# AdEMNEA.net
KiCad netlist of a schematic drawn in EasyEDA
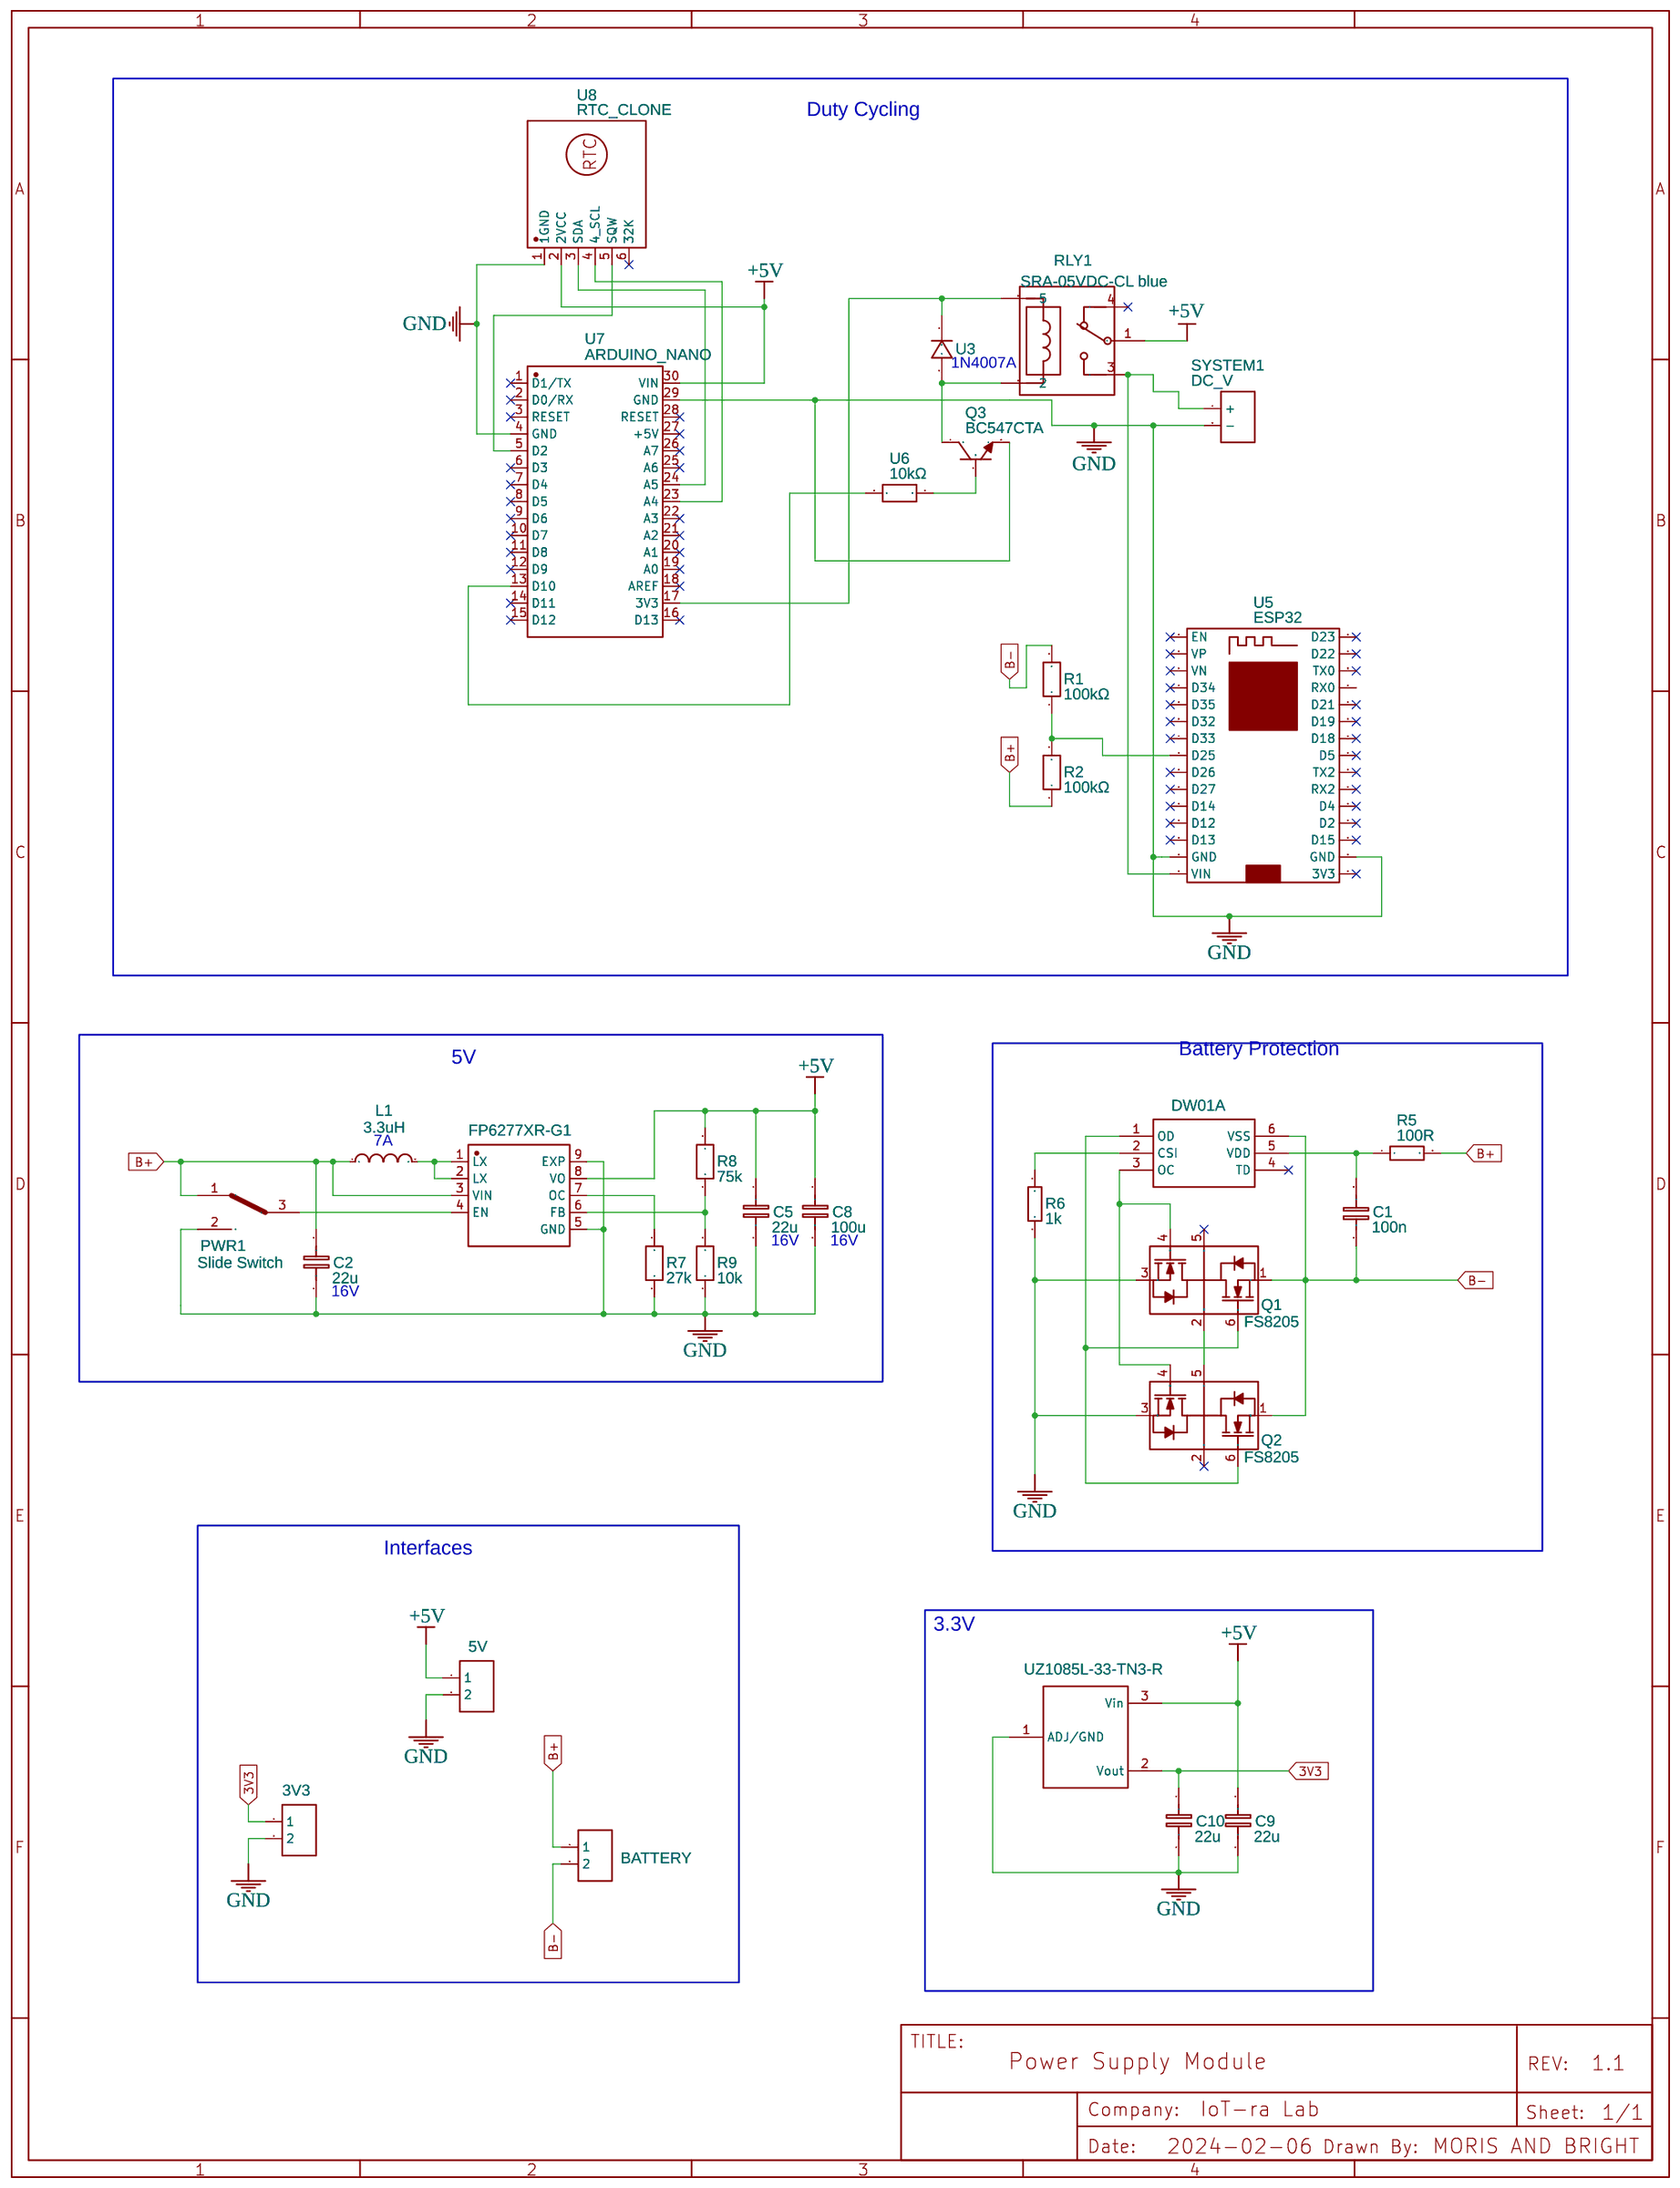
[diagram p0: schematic sheet]

(export (version "E")
  (design (tool "Eeschema 10.0.6"))
  (components
    (comp (ref "3V3")
      (value "Connector")
      (fields (field (name "Manufacturer Part") "2.54-1*2PFemale") (field (name "Manufacturer") "BOOMELE"))
      (libsource (lib "") (part "Unknown_305_-960"))
    )
    (comp (ref "5V")
      (value "Connector")
      (fields (field (name "Manufacturer Part") "2.54-1*2PFemale") (field (name "Manufacturer") "BOOMELE"))
      (libsource (lib "") (part "Unknown_410_-1045"))
    )
    (comp (ref "BATTERY")
      (value "Connector")
      (fields (field (name "Manufacturer Part") "2.54-1*2PFemale") (field (name "Manufacturer") "BOOMELE"))
      (libsource (lib "") (part "Unknown_480_-945"))
    )
    (comp (ref "C1")
      (value "100n")
      (fields (field (name "Manufacturer Part") "CC0805KRX7R9BB104") (field (name "Manufacturer") "YAGEO"))
      (libsource (lib "") (part "Cap_0805_EU_1"))
    )
    (comp (ref "C2")
      (value "22u")
      (fields (field (name "Manufacturer Part") "CL21A226MAQNNNE") (field (name "Manufacturer") "SAMSUNG"))
      (libsource (lib "") (part "Cap_0805_EU_2"))
    )
    (comp (ref "C5")
      (value "22u")
      (fields (field (name "Manufacturer Part") "CL21A226MAQNNNE") (field (name "Manufacturer") "SAMSUNG"))
      (libsource (lib "") (part "Cap_0805_EU"))
    )
    (comp (ref "C8")
      (value "100u")
      (fields (field (name "Manufacturer Part") "CL31A107MPHNNNE") (field (name "Manufacturer") "SAMSUNG"))
      (libsource (lib "") (part "Cap_0805_EU"))
    )
    (comp (ref "C9")
      (value "22u")
      (fields (field (name "Manufacturer Part") "CL21A226MAQNNNE") (field (name "Manufacturer") "SAMSUNG"))
      (libsource (lib "") (part "Cap_0805_EU"))
    )
    (comp (ref "C10")
      (value "22u")
      (fields (field (name "Manufacturer Part") "CL21A226MAQNNNE") (field (name "Manufacturer") "SAMSUNG"))
      (libsource (lib "") (part "Cap_0805_EU"))
    )
    (comp (ref "L1")
      (value "3.3uH")
      (fields (field (name "Manufacturer Part") "JSHC0650H-3R3M-G") (field (name "Manufacturer") "Jinlai"))
      (libsource (lib "") (part "JSHC0650H-3R3M-G"))
    )
    (comp (ref "PWR1")
      (value "Slide Switch")
      (fields (field (name "Manufacturer Part") "New SchematicLib"))
      (libsource (lib "") (part "Unknown_280_-1325"))
    )
    (comp (ref "Q1")
      (value "FS8205")
      (fields (field (name "Manufacturer") "FORTUNE"))
      (libsource (lib "") (part "FS8205"))
    )
    (comp (ref "Q2")
      (value "FS8205")
      (fields (field (name "Manufacturer") "FORTUNE"))
      (libsource (lib "") (part "FS8205"))
    )
    (comp (ref "Q3")
      (value "BC547CTA")
      (fields (field (name "Manufacturer") "onsemi(安森美)"))
      (libsource (lib "") (part "BC547CTA"))
    )
    (comp (ref "R1")
      (value "100kΩ")
      (fields
        (field (name "Manufacturer Part") "RNF14FAE100K")
        (field (name "Manufacturer") "SEI(Stackpole Electronics Inc.)")
      )
      (libsource (lib "") (part "RNF14FAE100K"))
    )
    (comp (ref "R2")
      (value "100kΩ")
      (fields
        (field (name "Manufacturer Part") "RNF14FAE100K")
        (field (name "Manufacturer") "SEI(Stackpole Electronics Inc.)")
      )
      (libsource (lib "") (part "RNF14FAE100K"))
    )
    (comp (ref "R5")
      (value "100R")
      (fields (field (name "Manufacturer Part") "0805W8F1000T5E") (field (name "Manufacturer") "UniOhm"))
      (libsource (lib "") (part "Res_0805(1/8W)_EU"))
    )
    (comp (ref "R6")
      (value "1k")
      (fields (field (name "Manufacturer Part") "0805W8F1001T5E") (field (name "Manufacturer") "UniOhm"))
      (libsource (lib "") (part "Res_0805(1/8W)_EU_2"))
    )
    (comp (ref "R7")
      (value "27k")
      (fields (field (name "Manufacturer Part") "0805W8F2702T5E") (field (name "Manufacturer") "UniOhm"))
      (libsource (lib "") (part "Res_0805(1/8W)_EU_1"))
    )
    (comp (ref "R8")
      (value "75k")
      (fields (field (name "Manufacturer Part") "0805W8F7502T5E") (field (name "Manufacturer") "UniOhm"))
      (libsource (lib "") (part "Res_0805(1/8W)_EU_1"))
    )
    (comp (ref "R9")
      (value "10k")
      (fields (field (name "Manufacturer Part") "0805W8F1002T5E") (field (name "Manufacturer") "UniOhm"))
      (libsource (lib "") (part "Res_0805(1/8W)_EU_1"))
    )
    (comp (ref "RLY1")
      (value "SRA-05VDC-CL blue")
      (fields (field (name "Manufacturer Part") "SRA-05VDC-CL") (field (name "Manufacturer") "松乐"))
      (libsource (lib "") (part "SRA-05VDC-CL blue"))
    )
    (comp (ref "SYSTEM1") (value "DC_V") (libsource (lib "") (part "DC_V")))
    (comp (ref "U1")
      (value "FP6277XR-G1")
      (fields (field (name "Manufacturer") "Feeling Technology"))
      (libsource (lib "") (part "FP6277XR-G1"))
    )
    (comp (ref "U2")
      (value "DW01A")
      (fields (field (name "Manufacturer") "FM"))
      (libsource (lib "") (part "Unknown_845_-1360"))
    )
    (comp (ref "U3")
      (value "1N4007A")
      (fields (field (name "Manufacturer") "LRC(乐山无线电)"))
      (libsource (lib "") (part "1N4007A"))
    )
    (comp (ref "U4")
      (value "UZ1085L-33-TN3-R")
      (fields (field (name "Manufacturer") "UTC"))
      (libsource (lib "") (part "UZ1085L-33-TN3-R"))
    )
    (comp (ref "U5") (value "ESP32") (libsource (lib "") (part "ESP32")))
    (comp (ref "U6")
      (value "10kΩ")
      (fields (field (name "Manufacturer Part") "FM0207FTE52-10K") (field (name "Manufacturer") "YAGEO(国巨)"))
      (libsource (lib "") (part "FM0207FTE52-10K"))
    )
    (comp (ref "U7") (value "ARDUINO_NANO") (libsource (lib "") (part "ARDUINO_NANO")))
    (comp (ref "U8") (value "RTC_CLONE") (libsource (lib "") (part "RTC_CLONE")))
  )
  (nets
    (net (code "1") (name "+5V") (class "Default")
      (node (ref "5V") (pin "1") (pinfunction "1_1") (pintype "input"))
      (node (ref "C5") (pin "1") (pinfunction "1_1") (pintype "unspecified"))
      (node (ref "C8") (pin "1") (pinfunction "1_1") (pintype "unspecified"))
      (node (ref "C9") (pin "1") (pinfunction "1_1") (pintype "unspecified"))
      (node (ref "R8") (pin "2") (pinfunction "2_2") (pintype "unspecified"))
      (node (ref "RLY1") (pin "1") (pinfunction "1_1") (pintype "unspecified"))
      (node (ref "U1") (pin "8") (pinfunction "VO_8") (pintype "unspecified"))
      (node (ref "U4") (pin "3") (pinfunction "Vin_3") (pintype "unspecified"))
      (node (ref "U7") (pin "30") (pinfunction "VIN_30") (pintype "unspecified"))
      (node (ref "U8") (pin "2") (pinfunction "2VCC_2") (pintype "unspecified"))
    )
    (net (code "2") (name "3V3") (class "Default")
      (node (ref "3V3") (pin "1") (pinfunction "1_1") (pintype "input"))
      (node (ref "C10") (pin "1") (pinfunction "1_1") (pintype "unspecified"))
      (node (ref "U4") (pin "2") (pinfunction "Vout_2") (pintype "unspecified"))
    )
    (net (code "3") (name "B+") (class "Default")
      (node (ref "BATTERY") (pin "1") (pinfunction "1_1") (pintype "input"))
      (node (ref "C2") (pin "1") (pinfunction "1_1") (pintype "unspecified"))
      (node (ref "L1") (pin "1") (pinfunction "1_1") (pintype "unspecified"))
      (node (ref "PWR1") (pin "1") (pinfunction "1_1") (pintype "unspecified"))
      (node (ref "R2") (pin "1") (pinfunction "1_1") (pintype "unspecified"))
      (node (ref "R5") (pin "2") (pinfunction "2_2") (pintype "unspecified"))
      (node (ref "U1") (pin "3") (pinfunction "VIN_3") (pintype "unspecified"))
    )
    (net (code "4") (name "B-") (class "Default")
      (node (ref "BATTERY") (pin "2") (pinfunction "2_2") (pintype "input"))
      (node (ref "C1") (pin "1") (pinfunction "1_1") (pintype "unspecified"))
      (node (ref "Q1") (pin "1") (pinfunction "S1_1") (pintype "unspecified"))
      (node (ref "Q2") (pin "1") (pinfunction "S1_1") (pintype "unspecified"))
      (node (ref "R1") (pin "2") (pinfunction "2_2") (pintype "unspecified"))
      (node (ref "U2") (pin "6") (pinfunction "VSS_6") (pintype "unspecified"))
    )
    (net (code "5") (name "GND") (class "Default")
      (node (ref "3V3") (pin "2") (pinfunction "2_2") (pintype "input"))
      (node (ref "5V") (pin "2") (pinfunction "2_2") (pintype "input"))
      (node (ref "C10") (pin "2") (pinfunction "2_2") (pintype "unspecified"))
      (node (ref "C2") (pin "2") (pinfunction "2_2") (pintype "unspecified"))
      (node (ref "C5") (pin "2") (pinfunction "2_2") (pintype "unspecified"))
      (node (ref "C8") (pin "2") (pinfunction "2_2") (pintype "unspecified"))
      (node (ref "C9") (pin "2") (pinfunction "2_2") (pintype "unspecified"))
      (node (ref "PWR1") (pin "2") (pinfunction "2_2") (pintype "unspecified"))
      (node (ref "Q1") (pin "3") (pinfunction "S2_3") (pintype "unspecified"))
      (node (ref "Q2") (pin "3") (pinfunction "S2_3") (pintype "unspecified"))
      (node (ref "Q3") (pin "3") (pinfunction "E_3") (pintype "input"))
      (node (ref "R6") (pin "1") (pinfunction "1_1") (pintype "unspecified"))
      (node (ref "R7") (pin "1") (pinfunction "1_1") (pintype "unspecified"))
      (node (ref "R9") (pin "1") (pinfunction "1_1") (pintype "unspecified"))
      (node (ref "SYSTEM1") (pin "2") (pinfunction "-_2") (pintype "unspecified"))
      (node (ref "U1") (pin "5") (pinfunction "GND_5") (pintype "unspecified"))
      (node (ref "U1") (pin "9") (pinfunction "EXP_9") (pintype "unspecified"))
      (node (ref "U4") (pin "1") (pinfunction "ADJ/GND_1") (pintype "unspecified"))
      (node (ref "U5") (pin "14") (pinfunction "GND_14") (pintype "unspecified"))
      (node (ref "U5") (pin "17") (pinfunction "GND_17") (pintype "unspecified"))
      (node (ref "U7") (pin "29") (pinfunction "GND_29") (pintype "unspecified"))
      (node (ref "U7") (pin "4") (pinfunction "GND_4") (pintype "unspecified"))
      (node (ref "U8") (pin "1") (pinfunction "1GND_1") (pintype "unspecified"))
    )
    (net (code "6") (name "Net-(L1-Pad2)") (class "Default")
      (node (ref "L1") (pin "2") (pinfunction "2_2") (pintype "unspecified"))
      (node (ref "U1") (pin "1") (pinfunction "LX_1") (pintype "unspecified"))
      (node (ref "U1") (pin "2") (pinfunction "LX_2") (pintype "unspecified"))
    )
    (net (code "7") (name "Net-(Q1-D12-Pad2)") (class "Default")
      (node (ref "Q1") (pin "2") (pinfunction "D12_2") (pintype "unspecified"))
      (node (ref "Q2") (pin "5") (pinfunction "D12_5") (pintype "unspecified"))
    )
    (net (code "8") (name "Net-(Q1-G1)") (class "Default")
      (node (ref "Q1") (pin "6") (pinfunction "G1_6") (pintype "unspecified"))
      (node (ref "Q2") (pin "6") (pinfunction "G1_6") (pintype "unspecified"))
      (node (ref "U2") (pin "1") (pinfunction "OD_1") (pintype "unspecified"))
    )
    (net (code "9") (name "Net-(Q1-G2)") (class "Default")
      (node (ref "Q1") (pin "4") (pinfunction "G2_4") (pintype "unspecified"))
      (node (ref "Q2") (pin "4") (pinfunction "G2_4") (pintype "unspecified"))
      (node (ref "U2") (pin "3") (pinfunction "OC_3") (pintype "unspecified"))
    )
    (net (code "10") (name "Net-(Q3-B)") (class "Default")
      (node (ref "Q3") (pin "2") (pinfunction "B_2") (pintype "input"))
      (node (ref "U6") (pin "2") (pinfunction "2_2") (pintype "unspecified"))
    )
    (net (code "11") (name "Net-(Q3-C)") (class "Default")
      (node (ref "Q3") (pin "1") (pinfunction "C_1") (pintype "input"))
      (node (ref "RLY1") (pin "2") (pinfunction "2_2") (pintype "unspecified"))
      (node (ref "U3") (pin "2") (pinfunction "2_2") (pintype "unspecified"))
    )
    (net (code "12") (name "Net-(SYSTEM1-+)") (class "Default")
      (node (ref "RLY1") (pin "3") (pinfunction "3_3") (pintype "unspecified"))
      (node (ref "SYSTEM1") (pin "1") (pinfunction "+_1") (pintype "unspecified"))
      (node (ref "U5") (pin "15") (pinfunction "VIN_15") (pintype "unspecified"))
    )
    (net (code "13") (name "Net-(U1-EN)") (class "Default")
      (node (ref "PWR1") (pin "3") (pinfunction "3_3") (pintype "unspecified"))
      (node (ref "U1") (pin "4") (pinfunction "EN_4") (pintype "unspecified"))
    )
    (net (code "14") (name "Net-(U1-FB)") (class "Default")
      (node (ref "R8") (pin "1") (pinfunction "1_1") (pintype "unspecified"))
      (node (ref "R9") (pin "2") (pinfunction "2_2") (pintype "unspecified"))
      (node (ref "U1") (pin "6") (pinfunction "FB_6") (pintype "unspecified"))
    )
    (net (code "15") (name "Net-(U1-OC)") (class "Default")
      (node (ref "R7") (pin "2") (pinfunction "2_2") (pintype "unspecified"))
      (node (ref "U1") (pin "7") (pinfunction "OC_7") (pintype "unspecified"))
    )
    (net (code "16") (name "Net-(U2-CSI)") (class "Default")
      (node (ref "R6") (pin "2") (pinfunction "2_2") (pintype "unspecified"))
      (node (ref "U2") (pin "2") (pinfunction "CSI_2") (pintype "unspecified"))
    )
    (net (code "17") (name "Net-(U2-VDD)") (class "Default")
      (node (ref "C1") (pin "2") (pinfunction "2_2") (pintype "unspecified"))
      (node (ref "R5") (pin "1") (pinfunction "1_1") (pintype "unspecified"))
      (node (ref "U2") (pin "5") (pinfunction "VDD_5") (pintype "unspecified"))
    )
    (net (code "18") (name "Net-(U5-D25)") (class "Default")
      (node (ref "R1") (pin "1") (pinfunction "1_1") (pintype "unspecified"))
      (node (ref "R2") (pin "2") (pinfunction "2_2") (pintype "unspecified"))
      (node (ref "U5") (pin "8") (pinfunction "D25_8") (pintype "unspecified"))
    )
    (net (code "19") (name "Net-(U7-3V3)") (class "Default")
      (node (ref "RLY1") (pin "5") (pinfunction "5_5") (pintype "unspecified"))
      (node (ref "U3") (pin "1") (pinfunction "1_1") (pintype "unspecified"))
      (node (ref "U7") (pin "17") (pinfunction "3V3_17") (pintype "unspecified"))
    )
    (net (code "20") (name "Net-(U7-A4)") (class "Default")
      (node (ref "U7") (pin "23") (pinfunction "A4_23") (pintype "unspecified"))
      (node (ref "U8") (pin "4") (pinfunction "4_SCL_4") (pintype "unspecified"))
    )
    (net (code "21") (name "Net-(U7-A5)") (class "Default")
      (node (ref "U7") (pin "24") (pinfunction "A5_24") (pintype "unspecified"))
      (node (ref "U8") (pin "3") (pinfunction "SDA_3") (pintype "unspecified"))
    )
    (net (code "22") (name "Net-(U7-D2)") (class "Default")
      (node (ref "U7") (pin "5") (pinfunction "D2_5") (pintype "unspecified"))
      (node (ref "U8") (pin "5") (pinfunction "SQW_5") (pintype "unspecified"))
    )
    (net (code "23") (name "Net-(U7-D10)") (class "Default")
      (node (ref "U6") (pin "1") (pinfunction "1_1") (pintype "unspecified"))
      (node (ref "U7") (pin "13") (pinfunction "D10_13") (pintype "unspecified"))
    )
    (net (code "24") (name "unconnected-(Q1-D12-Pad5)") (class "Default")
      (node (ref "Q1") (pin "5") (pinfunction "D12_5") (pintype "unspecified+no_connect"))
    )
    (net (code "25") (name "unconnected-(Q2-D12-Pad2)") (class "Default")
      (node (ref "Q2") (pin "2") (pinfunction "D12_2") (pintype "unspecified+no_connect"))
    )
    (net (code "26") (name "unconnected-(RLY1-Pad4)") (class "Default")
      (node (ref "RLY1") (pin "4") (pinfunction "4_4") (pintype "unspecified+no_connect"))
    )
    (net (code "27") (name "unconnected-(U2-TD-Pad4)") (class "Default")
      (node (ref "U2") (pin "4") (pinfunction "TD_4") (pintype "unspecified+no_connect"))
    )
    (net (code "28") (name "unconnected-(U5-3V3-Pad16)") (class "Default")
      (node (ref "U5") (pin "16") (pinfunction "3V3_16") (pintype "unspecified+no_connect"))
    )
    (net (code "29") (name "unconnected-(U5-D2-Pad19)") (class "Default")
      (node (ref "U5") (pin "19") (pinfunction "D2_19") (pintype "unspecified+no_connect"))
    )
    (net (code "30") (name "unconnected-(U5-D4-Pad20)") (class "Default")
      (node (ref "U5") (pin "20") (pinfunction "D4_20") (pintype "unspecified+no_connect"))
    )
    (net (code "31") (name "unconnected-(U5-D5-Pad23)") (class "Default")
      (node (ref "U5") (pin "23") (pinfunction "D5_23") (pintype "unspecified+no_connect"))
    )
    (net (code "32") (name "unconnected-(U5-D12-Pad12)") (class "Default")
      (node (ref "U5") (pin "12") (pinfunction "D12_12") (pintype "unspecified+no_connect"))
    )
    (net (code "33") (name "unconnected-(U5-D13-Pad13)") (class "Default")
      (node (ref "U5") (pin "13") (pinfunction "D13_13") (pintype "unspecified+no_connect"))
    )
    (net (code "34") (name "unconnected-(U5-D14-Pad11)") (class "Default")
      (node (ref "U5") (pin "11") (pinfunction "D14_11") (pintype "unspecified+no_connect"))
    )
    (net (code "35") (name "unconnected-(U5-D15-Pad18)") (class "Default")
      (node (ref "U5") (pin "18") (pinfunction "D15_18") (pintype "unspecified+no_connect"))
    )
    (net (code "36") (name "unconnected-(U5-D18-Pad24)") (class "Default")
      (node (ref "U5") (pin "24") (pinfunction "D18_24") (pintype "unspecified+no_connect"))
    )
    (net (code "37") (name "unconnected-(U5-D19-Pad25)") (class "Default")
      (node (ref "U5") (pin "25") (pinfunction "D19_25") (pintype "unspecified+no_connect"))
    )
    (net (code "38") (name "unconnected-(U5-D21-Pad26)") (class "Default")
      (node (ref "U5") (pin "26") (pinfunction "D21_26") (pintype "unspecified+no_connect"))
    )
    (net (code "39") (name "unconnected-(U5-D22-Pad29)") (class "Default")
      (node (ref "U5") (pin "29") (pinfunction "D22_29") (pintype "unspecified+no_connect"))
    )
    (net (code "40") (name "unconnected-(U5-D23-Pad30)") (class "Default")
      (node (ref "U5") (pin "30") (pinfunction "D23_30") (pintype "unspecified+no_connect"))
    )
    (net (code "41") (name "unconnected-(U5-D26-Pad9)") (class "Default")
      (node (ref "U5") (pin "9") (pinfunction "D26_9") (pintype "unspecified+no_connect"))
    )
    (net (code "42") (name "unconnected-(U5-D27-Pad10)") (class "Default")
      (node (ref "U5") (pin "10") (pinfunction "D27_10") (pintype "unspecified+no_connect"))
    )
    (net (code "43") (name "unconnected-(U5-D32-Pad6)") (class "Default")
      (node (ref "U5") (pin "6") (pinfunction "D32_6") (pintype "unspecified+no_connect"))
    )
    (net (code "44") (name "unconnected-(U5-D33-Pad7)") (class "Default")
      (node (ref "U5") (pin "7") (pinfunction "D33_7") (pintype "unspecified+no_connect"))
    )
    (net (code "45") (name "unconnected-(U5-D34-Pad4)") (class "Default")
      (node (ref "U5") (pin "4") (pinfunction "D34_4") (pintype "unspecified+no_connect"))
    )
    (net (code "46") (name "unconnected-(U5-D35-Pad5)") (class "Default")
      (node (ref "U5") (pin "5") (pinfunction "D35_5") (pintype "unspecified+no_connect"))
    )
    (net (code "47") (name "unconnected-(U5-EN-Pad1)") (class "Default")
      (node (ref "U5") (pin "1") (pinfunction "EN_1") (pintype "unspecified+no_connect"))
    )
    (net (code "48") (name "unconnected-(U5-RX0-Pad27)") (class "Default")
      (node (ref "U5") (pin "27") (pinfunction "RX0_27") (pintype "unspecified"))
    )
    (net (code "49") (name "unconnected-(U5-RX2-Pad21)") (class "Default")
      (node (ref "U5") (pin "21") (pinfunction "RX2_21") (pintype "unspecified+no_connect"))
    )
    (net (code "50") (name "unconnected-(U5-TX0-Pad28)") (class "Default")
      (node (ref "U5") (pin "28") (pinfunction "TX0_28") (pintype "unspecified+no_connect"))
    )
    (net (code "51") (name "unconnected-(U5-TX2-Pad22)") (class "Default")
      (node (ref "U5") (pin "22") (pinfunction "TX2_22") (pintype "unspecified+no_connect"))
    )
    (net (code "52") (name "unconnected-(U5-VN-Pad3)") (class "Default")
      (node (ref "U5") (pin "3") (pinfunction "VN_3") (pintype "unspecified+no_connect"))
    )
    (net (code "53") (name "unconnected-(U5-VP-Pad2)") (class "Default")
      (node (ref "U5") (pin "2") (pinfunction "VP_2") (pintype "unspecified+no_connect"))
    )
    (net (code "54") (name "unconnected-(U7-+5V-Pad27)") (class "Default")
      (node (ref "U7") (pin "27") (pinfunction "+5V_27") (pintype "unspecified+no_connect"))
    )
    (net (code "55") (name "unconnected-(U7-A0-Pad19)") (class "Default")
      (node (ref "U7") (pin "19") (pinfunction "A0_19") (pintype "unspecified+no_connect"))
    )
    (net (code "56") (name "unconnected-(U7-A1-Pad20)") (class "Default")
      (node (ref "U7") (pin "20") (pinfunction "A1_20") (pintype "unspecified+no_connect"))
    )
    (net (code "57") (name "unconnected-(U7-A2-Pad21)") (class "Default")
      (node (ref "U7") (pin "21") (pinfunction "A2_21") (pintype "unspecified+no_connect"))
    )
    (net (code "58") (name "unconnected-(U7-A3-Pad22)") (class "Default")
      (node (ref "U7") (pin "22") (pinfunction "A3_22") (pintype "unspecified+no_connect"))
    )
    (net (code "59") (name "unconnected-(U7-A6-Pad25)") (class "Default")
      (node (ref "U7") (pin "25") (pinfunction "A6_25") (pintype "unspecified+no_connect"))
    )
    (net (code "60") (name "unconnected-(U7-A7-Pad26)") (class "Default")
      (node (ref "U7") (pin "26") (pinfunction "A7_26") (pintype "unspecified+no_connect"))
    )
    (net (code "61") (name "unconnected-(U7-AREF-Pad18)") (class "Default")
      (node (ref "U7") (pin "18") (pinfunction "AREF_18") (pintype "unspecified+no_connect"))
    )
    (net (code "62") (name "unconnected-(U7-D0{slash}RX-Pad2)") (class "Default")
      (node (ref "U7") (pin "2") (pinfunction "D0/RX_2") (pintype "unspecified+no_connect"))
    )
    (net (code "63") (name "unconnected-(U7-D1{slash}TX-Pad1)") (class "Default")
      (node (ref "U7") (pin "1") (pinfunction "D1/TX_1") (pintype "unspecified+no_connect"))
    )
    (net (code "64") (name "unconnected-(U7-D3-Pad6)") (class "Default")
      (node (ref "U7") (pin "6") (pinfunction "D3_6") (pintype "unspecified+no_connect"))
    )
    (net (code "65") (name "unconnected-(U7-D4-Pad7)") (class "Default")
      (node (ref "U7") (pin "7") (pinfunction "D4_7") (pintype "unspecified+no_connect"))
    )
    (net (code "66") (name "unconnected-(U7-D5-Pad8)") (class "Default")
      (node (ref "U7") (pin "8") (pinfunction "D5_8") (pintype "unspecified+no_connect"))
    )
    (net (code "67") (name "unconnected-(U7-D6-Pad9)") (class "Default")
      (node (ref "U7") (pin "9") (pinfunction "D6_9") (pintype "unspecified+no_connect"))
    )
    (net (code "68") (name "unconnected-(U7-D7-Pad10)") (class "Default")
      (node (ref "U7") (pin "10") (pinfunction "D7_10") (pintype "unspecified+no_connect"))
    )
    (net (code "69") (name "unconnected-(U7-D8-Pad11)") (class "Default")
      (node (ref "U7") (pin "11") (pinfunction "D8_11") (pintype "unspecified+no_connect"))
    )
    (net (code "70") (name "unconnected-(U7-D9-Pad12)") (class "Default")
      (node (ref "U7") (pin "12") (pinfunction "D9_12") (pintype "unspecified+no_connect"))
    )
    (net (code "71") (name "unconnected-(U7-D11-Pad14)") (class "Default")
      (node (ref "U7") (pin "14") (pinfunction "D11_14") (pintype "unspecified+no_connect"))
    )
    (net (code "72") (name "unconnected-(U7-D12-Pad15)") (class "Default")
      (node (ref "U7") (pin "15") (pinfunction "D12_15") (pintype "unspecified+no_connect"))
    )
    (net (code "73") (name "unconnected-(U7-D13-Pad16)") (class "Default")
      (node (ref "U7") (pin "16") (pinfunction "D13_16") (pintype "unspecified+no_connect"))
    )
    (net (code "74") (name "unconnected-(U7-RESET-Pad3)") (class "Default")
      (node (ref "U7") (pin "3") (pinfunction "RESET_3") (pintype "unspecified+no_connect"))
    )
    (net (code "75") (name "unconnected-(U7-RESET-Pad28)") (class "Default")
      (node (ref "U7") (pin "28") (pinfunction "RESET_28") (pintype "unspecified+no_connect"))
    )
    (net (code "76") (name "unconnected-(U8-32K-Pad6)") (class "Default")
      (node (ref "U8") (pin "6") (pinfunction "32K_6") (pintype "unspecified+no_connect"))
    )
  )
)
